# Microcontroller.net
KiCad netlist of a schematic drawn in Altium Designer
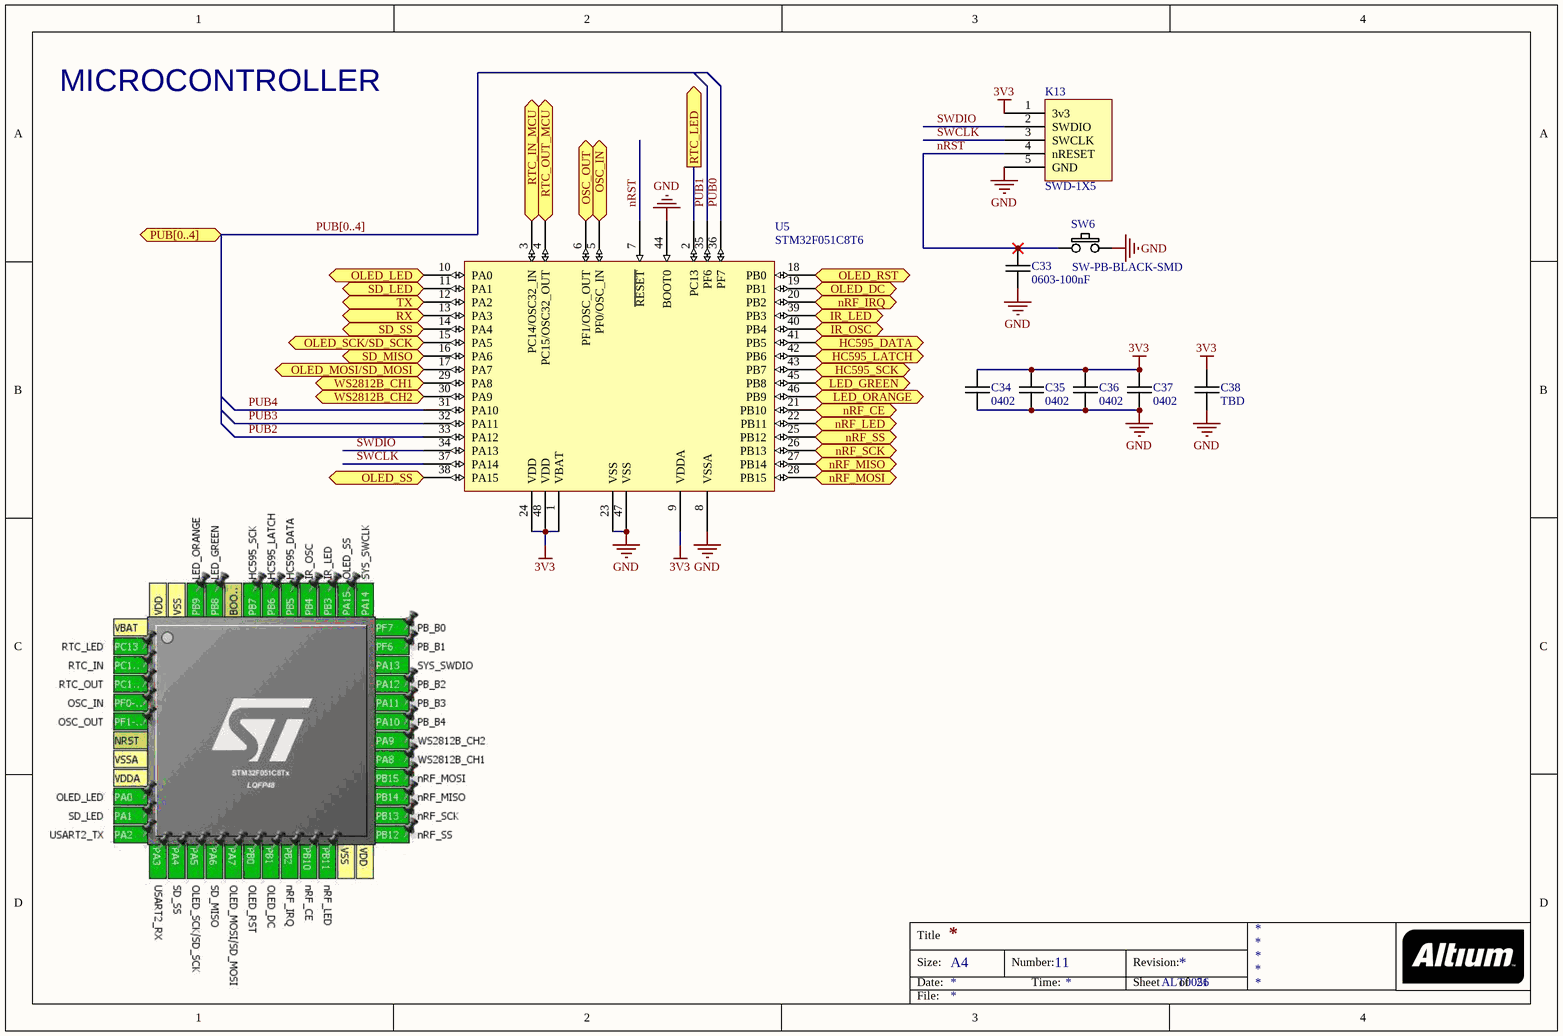
[diagram p0: Microcontroller.SchDoc]

(export (version "E")
  (design (tool "Eeschema 10.0.6"))
  (components
    (comp (ref "C33")
      (value "0603-100nF")
      (footprint "0603C-TBD")
      (description "CAPACITOR 0603 CERAMIC VALUE TO BE DETERMINED")
      (libsource (lib "RVA_Altium_Library") (part "0603C-TBD"))
    )
    (comp (ref "C34")
      (value "0402")
      (footprint "0402C-TBD")
      (description "CAPACITOR 0402 CERAMIC")
      (libsource (lib "vh_altium_library") (part "0402C-TBD"))
    )
    (comp (ref "C35")
      (value "0402")
      (footprint "0402C-TBD")
      (description "CAPACITOR 0402 CERAMIC")
      (libsource (lib "vh_altium_library") (part "0402C-TBD"))
    )
    (comp (ref "C36")
      (value "0402")
      (footprint "0402C-TBD")
      (description "CAPACITOR 0402 CERAMIC")
      (libsource (lib "vh_altium_library") (part "0402C-TBD"))
    )
    (comp (ref "C37")
      (value "0402")
      (footprint "0402C-TBD")
      (description "CAPACITOR 0402 CERAMIC")
      (libsource (lib "vh_altium_library") (part "0402C-TBD"))
    )
    (comp (ref "C38")
      (value "TBD")
      (footprint "1210C-GENERIC")
      (description "CAPACITOR 1210 CERAMIC VALUE TO BE DETERMINED")
      (libsource (lib "RVA_Altium_Library") (part "Passives_Capacitors_1210_1210C-TBD"))
    )
    (comp (ref "K13")
      (value "SWD-1X5")
      (footprint "HEADER-1X5")
      (description "SWD PINHEADER 1X5")
      (libsource (lib "RVA_Altium_Library") (part "SWD-1X5"))
    )
    (comp (ref "SW6")
      (value "SW-PB-BLACK-SMD")
      (footprint "SW-PB-SMD")
      (description "PUSHBUTTON SWITCH 6MM SMD")
      (libsource (lib "RVA_Altium_Library") (part "SW-PB-BLACK-SMD"))
    )
    (comp (ref "U5")
      (value "STM32F051C8T6")
      (footprint "LQFP48_N")
      (libsource (lib "RVA_Altium_Library") (part "STM32F051C8T6"))
    )
  )
  (nets
    (net (code "1") (name "/HC595_DATA") (class "Default")
      (node (ref "U5") (pin "41") (pinfunction "PB5_41") (pintype "bidirectional"))
    )
    (net (code "2") (name "/HC595_LATCH") (class "Default")
      (node (ref "U5") (pin "42") (pinfunction "PB6_42") (pintype "bidirectional"))
    )
    (net (code "3") (name "/HC595_SCK") (class "Default")
      (node (ref "U5") (pin "43") (pinfunction "PB7_43") (pintype "bidirectional"))
    )
    (net (code "4") (name "/IR_LED") (class "Default")
      (node (ref "U5") (pin "39") (pinfunction "PB3_39") (pintype "bidirectional"))
    )
    (net (code "5") (name "/IR_OSC") (class "Default")
      (node (ref "U5") (pin "40") (pinfunction "PB4_40") (pintype "bidirectional"))
    )
    (net (code "6") (name "/LED_GREEN") (class "Default")
      (node (ref "U5") (pin "45") (pinfunction "PB8_45") (pintype "bidirectional"))
    )
    (net (code "7") (name "/LED_ORANGE") (class "Default")
      (node (ref "U5") (pin "46") (pinfunction "PB9_46") (pintype "bidirectional"))
    )
    (net (code "8") (name "/OLED_DC") (class "Default")
      (node (ref "U5") (pin "19") (pinfunction "PB1_19") (pintype "bidirectional"))
    )
    (net (code "9") (name "/OLED_LED") (class "Default")
      (node (ref "U5") (pin "10") (pinfunction "PA0_10") (pintype "bidirectional"))
    )
    (net (code "10") (name "/OLED_MOSI{slash}SD_MOSI") (class "Default")
      (node (ref "U5") (pin "17") (pinfunction "PA7_17") (pintype "bidirectional"))
    )
    (net (code "11") (name "/OLED_RST") (class "Default")
      (node (ref "U5") (pin "18") (pinfunction "PB0_18") (pintype "bidirectional"))
    )
    (net (code "12") (name "/OLED_SCK{slash}SD_SCK") (class "Default")
      (node (ref "U5") (pin "15") (pinfunction "PA5_15") (pintype "bidirectional"))
    )
    (net (code "13") (name "/OLED_SS") (class "Default")
      (node (ref "U5") (pin "38") (pinfunction "PA15_38") (pintype "bidirectional"))
    )
    (net (code "14") (name "/OSC_IN") (class "Default")
      (node (ref "U5") (pin "5") (pinfunction "PF0/OSC_IN_5") (pintype "bidirectional"))
    )
    (net (code "15") (name "/OSC_OUT") (class "Default")
      (node (ref "U5") (pin "6") (pinfunction "PF1/OSC_OUT_6") (pintype "bidirectional"))
    )
    (net (code "16") (name "/PUB0") (class "Default")
      (node (ref "U5") (pin "36") (pinfunction "PF7_36") (pintype "bidirectional"))
    )
    (net (code "17") (name "/PUB1") (class "Default")
      (node (ref "U5") (pin "35") (pinfunction "PF6_35") (pintype "bidirectional"))
    )
    (net (code "18") (name "/PUB2") (class "Default")
      (node (ref "U5") (pin "33") (pinfunction "PA12_33") (pintype "bidirectional"))
    )
    (net (code "19") (name "/PUB3") (class "Default")
      (node (ref "U5") (pin "32") (pinfunction "PA11_32") (pintype "bidirectional"))
    )
    (net (code "20") (name "/PUB4") (class "Default")
      (node (ref "U5") (pin "31") (pinfunction "PA10_31") (pintype "bidirectional"))
    )
    (net (code "22") (name "/RTC_IN_MCU") (class "Default")
      (node (ref "U5") (pin "3") (pinfunction "PC14/OSC32_IN_3") (pintype "bidirectional"))
    )
    (net (code "23") (name "/RTC_LED") (class "Default")
      (node (ref "U5") (pin "2") (pinfunction "PC13_2") (pintype "bidirectional"))
    )
    (net (code "24") (name "/RTC_OUT_MCU") (class "Default")
      (node (ref "U5") (pin "4") (pinfunction "PC15/OSC32_OUT_4") (pintype "bidirectional"))
    )
    (net (code "25") (name "/RX") (class "Default")
      (node (ref "U5") (pin "13") (pinfunction "PA3_13") (pintype "bidirectional"))
    )
    (net (code "26") (name "/SD_LED") (class "Default")
      (node (ref "U5") (pin "11") (pinfunction "PA1_11") (pintype "bidirectional"))
    )
    (net (code "27") (name "/SD_MISO") (class "Default")
      (node (ref "U5") (pin "16") (pinfunction "PA6_16") (pintype "bidirectional"))
    )
    (net (code "28") (name "/SD_SS") (class "Default")
      (node (ref "U5") (pin "14") (pinfunction "PA4_14") (pintype "bidirectional"))
    )
    (net (code "29") (name "/SWCLK") (class "Default")
      (node (ref "K13") (pin "3") (pinfunction "SWCLK_3") (pintype "passive"))
      (node (ref "U5") (pin "37") (pinfunction "PA14_37") (pintype "bidirectional"))
    )
    (net (code "30") (name "/SWDIO") (class "Default")
      (node (ref "K13") (pin "2") (pinfunction "SWDIO_2") (pintype "passive"))
      (node (ref "U5") (pin "34") (pinfunction "PA13_34") (pintype "bidirectional"))
    )
    (net (code "31") (name "/TX") (class "Default")
      (node (ref "U5") (pin "12") (pinfunction "PA2_12") (pintype "bidirectional"))
    )
    (net (code "32") (name "/WS2812B_CH1") (class "Default")
      (node (ref "U5") (pin "29") (pinfunction "PA8_29") (pintype "bidirectional"))
    )
    (net (code "33") (name "/WS2812B_CH2") (class "Default")
      (node (ref "U5") (pin "30") (pinfunction "PA9_30") (pintype "bidirectional"))
    )
    (net (code "34") (name "/nRF_CE") (class "Default")
      (node (ref "U5") (pin "21") (pinfunction "PB10_21") (pintype "bidirectional"))
    )
    (net (code "35") (name "/nRF_IRQ") (class "Default")
      (node (ref "U5") (pin "20") (pinfunction "PB2_20") (pintype "bidirectional"))
    )
    (net (code "36") (name "/nRF_LED") (class "Default")
      (node (ref "U5") (pin "22") (pinfunction "PB11_22") (pintype "bidirectional"))
    )
    (net (code "37") (name "/nRF_MISO") (class "Default")
      (node (ref "U5") (pin "27") (pinfunction "PB14_27") (pintype "bidirectional"))
    )
    (net (code "38") (name "/nRF_MOSI") (class "Default")
      (node (ref "U5") (pin "28") (pinfunction "PB15_28") (pintype "bidirectional"))
    )
    (net (code "39") (name "/nRF_SCK") (class "Default")
      (node (ref "U5") (pin "26") (pinfunction "PB13_26") (pintype "bidirectional"))
    )
    (net (code "40") (name "/nRF_SS") (class "Default")
      (node (ref "U5") (pin "25") (pinfunction "PB12_25") (pintype "bidirectional"))
    )
    (net (code "41") (name "/nRST") (class "Default")
      (node (ref "C33") (pin "1") (pintype "passive"))
      (node (ref "K13") (pin "4") (pinfunction "nRESET_4") (pintype "passive"))
      (node (ref "SW6") (pin "1") (pintype "passive"))
      (node (ref "U5") (pin "7") (pinfunction "~{RESET}_7") (pintype "input"))
    )
    (net (code "42") (name "3V3") (class "Default")
      (node (ref "C34") (pin "1") (pintype "passive"))
      (node (ref "C35") (pin "1") (pintype "passive"))
      (node (ref "C36") (pin "1") (pintype "passive"))
      (node (ref "C37") (pin "1") (pintype "passive"))
      (node (ref "C38") (pin "1") (pintype "passive"))
      (node (ref "K13") (pin "1") (pinfunction "3v3_1") (pintype "passive"))
      (node (ref "U5") (pin "1") (pinfunction "VBAT_1") (pintype "power_in"))
      (node (ref "U5") (pin "24") (pinfunction "VDD_24") (pintype "power_in"))
      (node (ref "U5") (pin "48") (pinfunction "VDD_48") (pintype "power_in"))
      (node (ref "U5") (pin "9") (pinfunction "VDDA_9") (pintype "power_in"))
    )
    (net (code "43") (name "GND") (class "Default")
      (node (ref "C33") (pin "2") (pintype "passive"))
      (node (ref "C34") (pin "2") (pintype "passive"))
      (node (ref "C35") (pin "2") (pintype "passive"))
      (node (ref "C36") (pin "2") (pintype "passive"))
      (node (ref "C37") (pin "2") (pintype "passive"))
      (node (ref "C38") (pin "2") (pintype "passive"))
      (node (ref "K13") (pin "5") (pinfunction "GND_5") (pintype "passive"))
      (node (ref "SW6") (pin "2") (pintype "passive"))
      (node (ref "U5") (pin "23") (pinfunction "VSS_23") (pintype "power_in"))
      (node (ref "U5") (pin "44") (pinfunction "BOOT0_44") (pintype "input"))
      (node (ref "U5") (pin "47") (pinfunction "VSS_47") (pintype "power_in"))
      (node (ref "U5") (pin "8") (pinfunction "VSSA_8") (pintype "power_in"))
    )
  )
)
